# LM2596S_5_0.net
KiCad netlist of a schematic drawn in Altium Designer
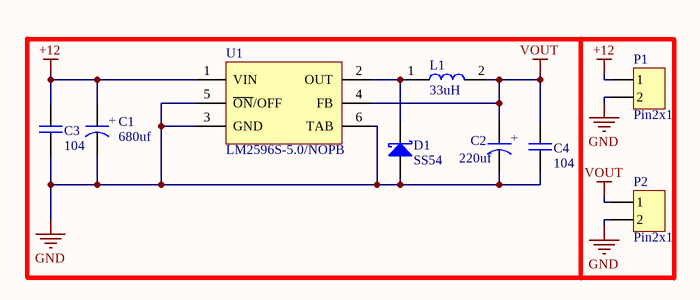
[diagram p0: LM2596S_5.0.SchDoc]

(export (version "E")
  (design (tool "Eeschema 10.0.6"))
  (components
    (comp (ref "C1")
      (value "680uf")
      (footprint "CAP-SMD-B")
      (description "CAP-SMD")
      (libsource (lib "LM2596S_5.0") (part "CAP-SMD"))
    )
    (comp (ref "C2")
      (value "220uf")
      (footprint "CAP-SMD-B")
      (description "CAP-SMD")
      (libsource (lib "LM2596S_5.0") (part "CAP-SMD"))
    )
    (comp (ref "C3") (value "104") (footprint "0603C") (libsource (lib "LM2596S_5.0") (part "CAP-SMT")))
    (comp (ref "C4") (value "104") (footprint "0603C") (libsource (lib "LM2596S_5.0") (part "CAP-SMT")))
    (comp (ref "D1") (value "SS54") (footprint "SMC") (libsource (lib "LM2596S_5.0") (part "DIO")))
    (comp (ref "L1") (value "33uH") (footprint "CDRH74") (libsource (lib "LM2596S_5.0") (part "L-CDRH74")))
    (comp (ref "P1")
      (value "Pin2x1")
      (footprint "5.08A-2PIN")
      (libsource (lib "LM2596S_5.0") (part "HEADER_2P"))
    )
    (comp (ref "P2")
      (value "Pin2x1")
      (footprint "5.08A-2PIN")
      (libsource (lib "LM2596S_5.0") (part "HEADER_2P"))
    )
    (comp (ref "U1")
      (value "LM2596S-5.0/NOPB")
      (footprint "TO263-5A")
      (description "SIMPLE SWITCHER® Power Converter 150 KHz 3A Step-Down Voltage Regulator, 5-pin TO-263, Pb-Free")
      (fields (field (name "MANUFACTURER") "Texas Instruments"))
      (libsource (lib "LM2596S_5.0") (part "LM2596S-5.0"))
    )
  )
  (nets
    (net (code "1") (name "+12") (class "Default")
      (node (ref "C1") (pin "2") (pinfunction "2_2") (pintype "passive"))
      (node (ref "C3") (pin "2") (pinfunction "2_2") (pintype "passive"))
      (node (ref "P1") (pin "1") (pinfunction "1_1") (pintype "passive"))
      (node (ref "U1") (pin "1") (pinfunction "VIN_1") (pintype "power_in"))
    )
    (net (code "2") (name "GND") (class "Default")
      (node (ref "C1") (pin "1") (pinfunction "1_1") (pintype "passive"))
      (node (ref "C2") (pin "1") (pinfunction "1_1") (pintype "passive"))
      (node (ref "C3") (pin "1") (pinfunction "1_1") (pintype "passive"))
      (node (ref "C4") (pin "1") (pinfunction "1_1") (pintype "passive"))
      (node (ref "D1") (pin "1") (pinfunction "1_1") (pintype "passive"))
      (node (ref "P1") (pin "2") (pinfunction "2_2") (pintype "passive"))
      (node (ref "P2") (pin "2") (pinfunction "2_2") (pintype "passive"))
      (node (ref "U1") (pin "3") (pinfunction "GND_3") (pintype "power_in"))
      (node (ref "U1") (pin "5") (pinfunction "~{ON}/OFF_5") (pintype "passive"))
      (node (ref "U1") (pin "6") (pinfunction "TAB_6") (pintype "power_in"))
    )
    (net (code "3") (name "Net-(U1-OUT)") (class "Default")
      (node (ref "D1") (pin "2") (pinfunction "2_2") (pintype "passive"))
      (node (ref "L1") (pin "1") (pinfunction "1_1") (pintype "passive"))
      (node (ref "U1") (pin "2") (pinfunction "OUT_2") (pintype "power_in"))
    )
    (net (code "4") (name "VOUT") (class "Default")
      (node (ref "C2") (pin "2") (pinfunction "2_2") (pintype "passive"))
      (node (ref "C4") (pin "2") (pinfunction "2_2") (pintype "passive"))
      (node (ref "L1") (pin "2") (pinfunction "2_2") (pintype "passive"))
      (node (ref "P2") (pin "1") (pinfunction "1_1") (pintype "passive"))
      (node (ref "U1") (pin "4") (pinfunction "FB_4") (pintype "passive"))
    )
  )
)
